# AD8495.net
KiCad netlist of a schematic drawn in Altium Designer
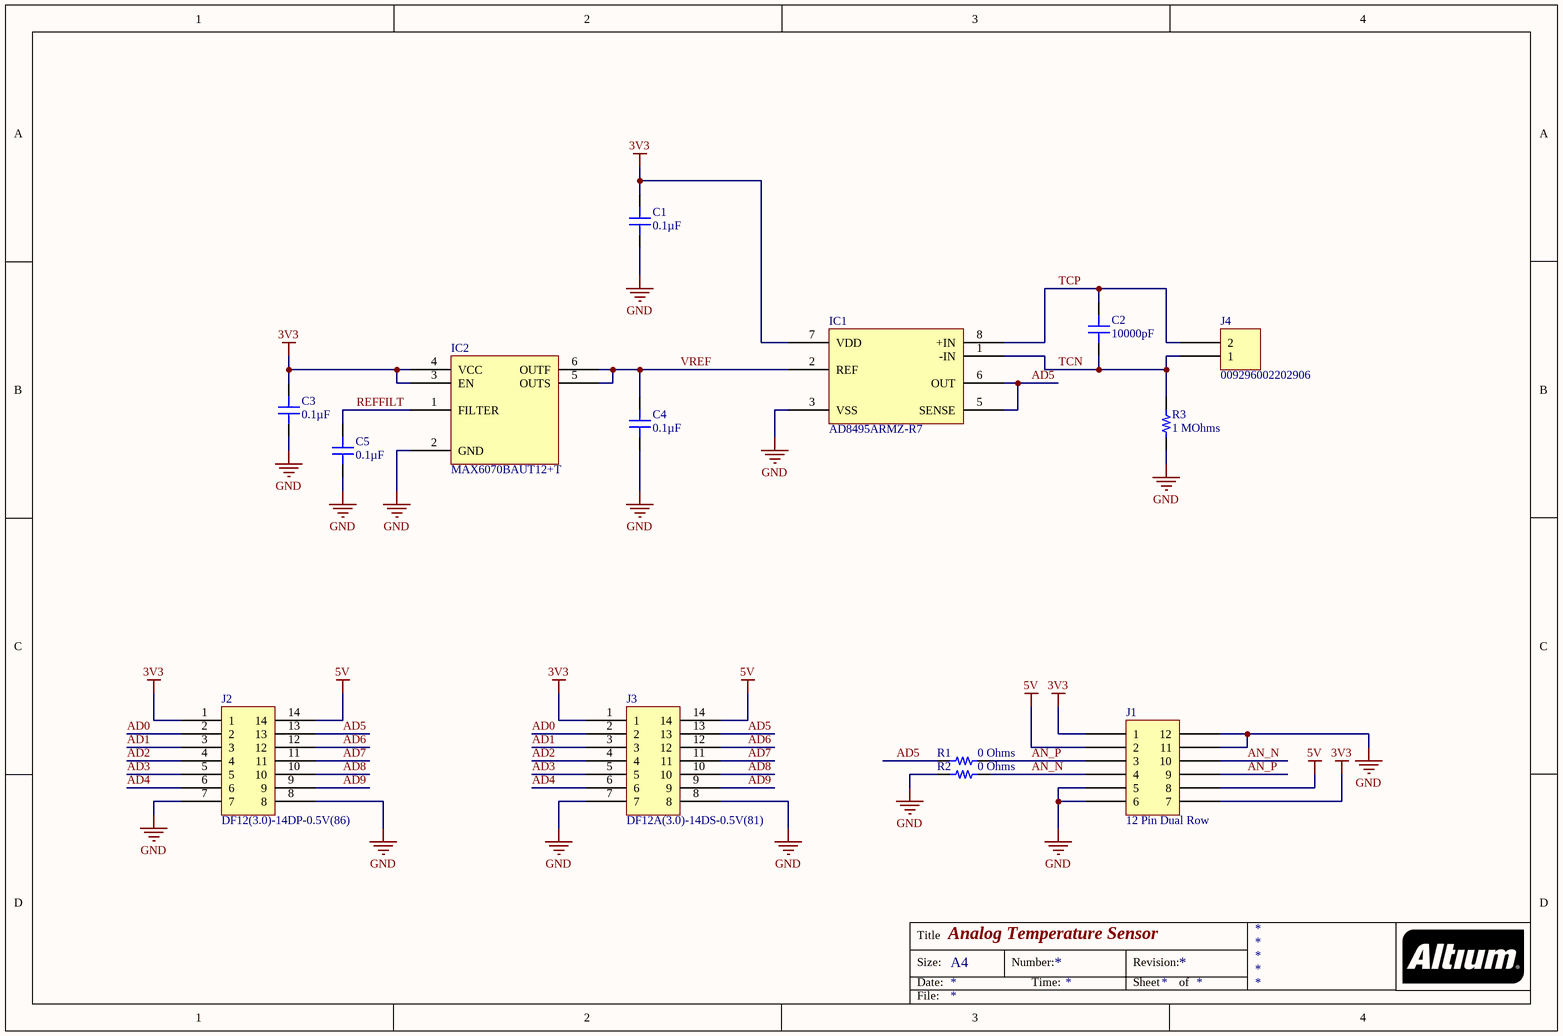
[diagram p0: AD8495.SchDoc]

(export (version "E")
  (design (tool "Eeschema 10.0.6"))
  (components
    (comp (ref "C1")
      (value "0.1µF")
      (footprint "CAP 0603_1608")
      (description "CAP CER 0.1UF 16V Y5V 0603")
      (fields (field (name "PART NUMBER") "CC0603ZRY5V7BB104") (field (name "MANUFACTURER") "Yageo"))
      (libsource (lib "altiumlibrary.com") (part "Capacitor"))
    )
    (comp (ref "C2")
      (value "10000pF")
      (footprint "CAP 0603_1608")
      (description "CAP CER 10000PF 100V X7R 0603")
      (fields
        (field (name "PART NUMBER") "CGA3E2X7R2A103M080AA")
        (field (name "MANUFACTURER") "TDK Corporation")
      )
      (libsource (lib "altiumlibrary.com") (part "Capacitor"))
    )
    (comp (ref "C3")
      (value "0.1µF")
      (footprint "CAP 0603_1608")
      (description "CAP CER 0.1UF 16V Y5V 0603")
      (fields (field (name "PART NUMBER") "CC0603ZRY5V7BB104") (field (name "MANUFACTURER") "Yageo"))
      (libsource (lib "altiumlibrary.com") (part "Capacitor"))
    )
    (comp (ref "C4")
      (value "0.1µF")
      (footprint "CAP 0603_1608")
      (description "CAP CER 0.1UF 16V Y5V 0603")
      (fields (field (name "PART NUMBER") "CC0603ZRY5V7BB104") (field (name "MANUFACTURER") "Yageo"))
      (libsource (lib "altiumlibrary.com") (part "Capacitor"))
    )
    (comp (ref "C5")
      (value "0.1µF")
      (footprint "CAP 0603_1608")
      (description "CAP CER 0.1UF 16V Y5V 0603")
      (fields (field (name "PART NUMBER") "CC0603ZRY5V7BB104") (field (name "MANUFACTURER") "Yageo"))
      (libsource (lib "altiumlibrary.com") (part "Capacitor"))
    )
    (comp (ref "IC1")
      (value "AD8495ARMZ-R7")
      (footprint "ANALOG MSOP-8 MS8 3X3MM")
      (description "IC THERMOCOUPLE A W/COMP 8MSOP")
      (fields (field (name "MANUFACTURER") "Analog Devices Inc."))
      (libsource (lib "altiumlibrary.com") (part "Analog AD849x"))
    )
    (comp (ref "IC2")
      (value "MAX6070BAUT12+T")
      (footprint "MAXIM SOT-23-6")
      (description "IC VREF SERIES 0.08% SOT23-6")
      (fields (field (name "MANUFACTURER") "Maxim Integrated") (field (name "TOLERANCE") "±0.08%"))
      (libsource (lib "altiumlibrary.com") (part "Maxim MAX6070"))
    )
    (comp (ref "J1")
      (value "12 Pin Dual Row")
      (footprint "TE 5650118-3 Card Edge")
      (libsource (lib "CelestialUseful") (part "12 Pin Dual Row"))
    )
    (comp (ref "J2")
      (value "DF12(3.0)-14DP-0.5V(86)")
      (footprint "HIROSE DF12 3.0-14DP-0.5V 86")
      (description "CONN HDR 14POS SMD GOLD")
      (fields (field (name "MANUFACTURER") "Hirose Electric Co Ltd"))
      (libsource (lib "altiumlibrary.com") (part "14 Pin Dual Row"))
    )
    (comp (ref "J3")
      (value "DF12A(3.0)-14DS-0.5V(81)")
      (footprint "HIROSE DF12A 3.0-14DS-0.5V 81")
      (description "CONN RCPT 14POS SMD GOLD")
      (fields (field (name "MANUFACTURER") "Hirose Electric Co Ltd"))
      (libsource (lib "altiumlibrary.com") (part "14 Pin Dual Row"))
    )
    (comp (ref "J4")
      (value "009296002202906")
      (footprint "AVX 9296002202806")
      (description "CONN WIRE POKE-IN 2POS SMD RA")
      (fields (field (name "MANUFACTURER") "AVX Corporation"))
      (libsource (lib "altiumlibrary.com") (part "2 Pin"))
    )
    (comp (ref "R1")
      (value "0 Ohms")
      (footprint "RES 0603_1608")
      (description "RES SMD 0 OHM JUMPER 1/10W 0603")
      (fields
        (field (name "PART NUMBER") "ERJ-3GEY0R00V")
        (field (name "MANUFACTURER") "Panasonic Electronic Components")
      )
      (libsource (lib "altiumlibrary.com") (part "Resistor"))
    )
    (comp (ref "R2")
      (value "0 Ohms")
      (footprint "RES 0603_1608")
      (description "RES SMD 0 OHM JUMPER 1/10W 0603")
      (fields
        (field (name "PART NUMBER") "ERJ-3GEY0R00V")
        (field (name "MANUFACTURER") "Panasonic Electronic Components")
      )
      (libsource (lib "altiumlibrary.com") (part "Resistor"))
    )
    (comp (ref "R3")
      (value "1 MOhms")
      (footprint "RES 0603_1608")
      (description "RES SMD 1M OHM 5% 1/5W 0603")
      (fields
        (field (name "PART NUMBER") "CRGH0603J1M0")
        (field (name "MANUFACTURER") "TE Connectivity Passive Product")
      )
      (libsource (lib "altiumlibrary.com") (part "Resistor"))
    )
  )
  (nets
    (net (code "1") (name "/AD0") (class "Default")
      (node (ref "J2") (pin "2") (pinfunction "2_2") (pintype "passive"))
      (node (ref "J3") (pin "2") (pinfunction "2_2") (pintype "passive"))
    )
    (net (code "2") (name "/AD1") (class "Default")
      (node (ref "J2") (pin "3") (pinfunction "3_3") (pintype "passive"))
      (node (ref "J3") (pin "3") (pinfunction "3_3") (pintype "passive"))
    )
    (net (code "3") (name "/AD2") (class "Default")
      (node (ref "J2") (pin "4") (pinfunction "4_4") (pintype "passive"))
      (node (ref "J3") (pin "4") (pinfunction "4_4") (pintype "passive"))
    )
    (net (code "4") (name "/AD3") (class "Default")
      (node (ref "J2") (pin "5") (pinfunction "5_5") (pintype "passive"))
      (node (ref "J3") (pin "5") (pinfunction "5_5") (pintype "passive"))
    )
    (net (code "5") (name "/AD4") (class "Default")
      (node (ref "J2") (pin "6") (pinfunction "6_6") (pintype "passive"))
      (node (ref "J3") (pin "6") (pinfunction "6_6") (pintype "passive"))
    )
    (net (code "6") (name "/AD5") (class "Default")
      (node (ref "IC1") (pin "5") (pinfunction "SENSE_5") (pintype "passive"))
      (node (ref "IC1") (pin "6") (pinfunction "OUT_6") (pintype "passive"))
      (node (ref "J2") (pin "13") (pinfunction "13_13") (pintype "passive"))
      (node (ref "J3") (pin "13") (pinfunction "13_13") (pintype "passive"))
      (node (ref "R1") (pin "1") (pinfunction "1_1") (pintype "passive"))
    )
    (net (code "7") (name "/AD6") (class "Default")
      (node (ref "J2") (pin "12") (pinfunction "12_12") (pintype "passive"))
      (node (ref "J3") (pin "12") (pinfunction "12_12") (pintype "passive"))
    )
    (net (code "8") (name "/AD7") (class "Default")
      (node (ref "J2") (pin "11") (pinfunction "11_11") (pintype "passive"))
      (node (ref "J3") (pin "11") (pinfunction "11_11") (pintype "passive"))
    )
    (net (code "9") (name "/AD8") (class "Default")
      (node (ref "J2") (pin "10") (pinfunction "10_10") (pintype "passive"))
      (node (ref "J3") (pin "10") (pinfunction "10_10") (pintype "passive"))
    )
    (net (code "10") (name "/AD9") (class "Default")
      (node (ref "J2") (pin "9") (pinfunction "9_9") (pintype "passive"))
      (node (ref "J3") (pin "9") (pinfunction "9_9") (pintype "passive"))
    )
    (net (code "11") (name "/AN_N") (class "Default")
      (node (ref "J1") (pin "10") (pinfunction "10_10") (pintype "passive"))
      (node (ref "J1") (pin "4") (pinfunction "4_4") (pintype "passive"))
      (node (ref "R2") (pin "2") (pinfunction "2_2") (pintype "passive"))
    )
    (net (code "12") (name "/AN_P") (class "Default")
      (node (ref "J1") (pin "3") (pinfunction "3_3") (pintype "passive"))
      (node (ref "J1") (pin "9") (pinfunction "9_9") (pintype "passive"))
      (node (ref "R1") (pin "2") (pinfunction "2_2") (pintype "passive"))
    )
    (net (code "13") (name "/REFFILT") (class "Default")
      (node (ref "C5") (pin "1") (pinfunction "1_1") (pintype "passive"))
      (node (ref "IC2") (pin "1") (pinfunction "FILTER_1") (pintype "passive"))
    )
    (net (code "14") (name "/TCN") (class "Default")
      (node (ref "C2") (pin "1") (pinfunction "1_1") (pintype "passive"))
      (node (ref "IC1") (pin "1") (pinfunction "-IN_1") (pintype "passive"))
      (node (ref "J4") (pin "1") (pinfunction "1_1") (pintype "passive"))
      (node (ref "R3") (pin "2") (pinfunction "2_2") (pintype "passive"))
    )
    (net (code "15") (name "/TCP") (class "Default")
      (node (ref "C2") (pin "2") (pinfunction "2_2") (pintype "passive"))
      (node (ref "IC1") (pin "8") (pinfunction "+IN_8") (pintype "passive"))
      (node (ref "J4") (pin "2") (pinfunction "2_2") (pintype "passive"))
    )
    (net (code "16") (name "/VREF") (class "Default")
      (node (ref "C4") (pin "1") (pinfunction "1_1") (pintype "passive"))
      (node (ref "IC1") (pin "2") (pinfunction "REF_2") (pintype "passive"))
      (node (ref "IC2") (pin "5") (pinfunction "OUTS_5") (pintype "passive"))
      (node (ref "IC2") (pin "6") (pinfunction "OUTF_6") (pintype "passive"))
    )
    (net (code "17") (name "3V3") (class "Default")
      (node (ref "C1") (pin "1") (pinfunction "1_1") (pintype "passive"))
      (node (ref "C3") (pin "1") (pinfunction "1_1") (pintype "passive"))
      (node (ref "IC1") (pin "7") (pinfunction "VDD_7") (pintype "passive"))
      (node (ref "IC2") (pin "3") (pinfunction "EN_3") (pintype "passive"))
      (node (ref "IC2") (pin "4") (pinfunction "VCC_4") (pintype "passive"))
      (node (ref "J1") (pin "1") (pinfunction "1_1") (pintype "passive"))
      (node (ref "J1") (pin "7") (pinfunction "7_7") (pintype "passive"))
      (node (ref "J2") (pin "1") (pinfunction "1_1") (pintype "passive"))
      (node (ref "J3") (pin "1") (pinfunction "1_1") (pintype "passive"))
    )
    (net (code "18") (name "5V") (class "Default")
      (node (ref "J1") (pin "2") (pinfunction "2_2") (pintype "passive"))
      (node (ref "J1") (pin "8") (pinfunction "8_8") (pintype "passive"))
      (node (ref "J2") (pin "14") (pinfunction "14_14") (pintype "passive"))
      (node (ref "J3") (pin "14") (pinfunction "14_14") (pintype "passive"))
    )
    (net (code "19") (name "GND") (class "Default")
      (node (ref "C1") (pin "2") (pinfunction "2_2") (pintype "passive"))
      (node (ref "C3") (pin "2") (pinfunction "2_2") (pintype "passive"))
      (node (ref "C4") (pin "2") (pinfunction "2_2") (pintype "passive"))
      (node (ref "C5") (pin "2") (pinfunction "2_2") (pintype "passive"))
      (node (ref "IC1") (pin "3") (pinfunction "VSS_3") (pintype "passive"))
      (node (ref "IC2") (pin "2") (pinfunction "GND_2") (pintype "passive"))
      (node (ref "J1") (pin "11") (pinfunction "11_11") (pintype "passive"))
      (node (ref "J1") (pin "12") (pinfunction "12_12") (pintype "passive"))
      (node (ref "J1") (pin "5") (pinfunction "5_5") (pintype "passive"))
      (node (ref "J1") (pin "6") (pinfunction "6_6") (pintype "passive"))
      (node (ref "J2") (pin "7") (pinfunction "7_7") (pintype "passive"))
      (node (ref "J2") (pin "8") (pinfunction "8_8") (pintype "passive"))
      (node (ref "J3") (pin "7") (pinfunction "7_7") (pintype "passive"))
      (node (ref "J3") (pin "8") (pinfunction "8_8") (pintype "passive"))
      (node (ref "R2") (pin "1") (pinfunction "1_1") (pintype "passive"))
      (node (ref "R3") (pin "1") (pinfunction "1_1") (pintype "passive"))
    )
  )
)
